# ou6_cs-ctrl_V1_1.net
KiCad netlist of a schematic drawn in EAGLE
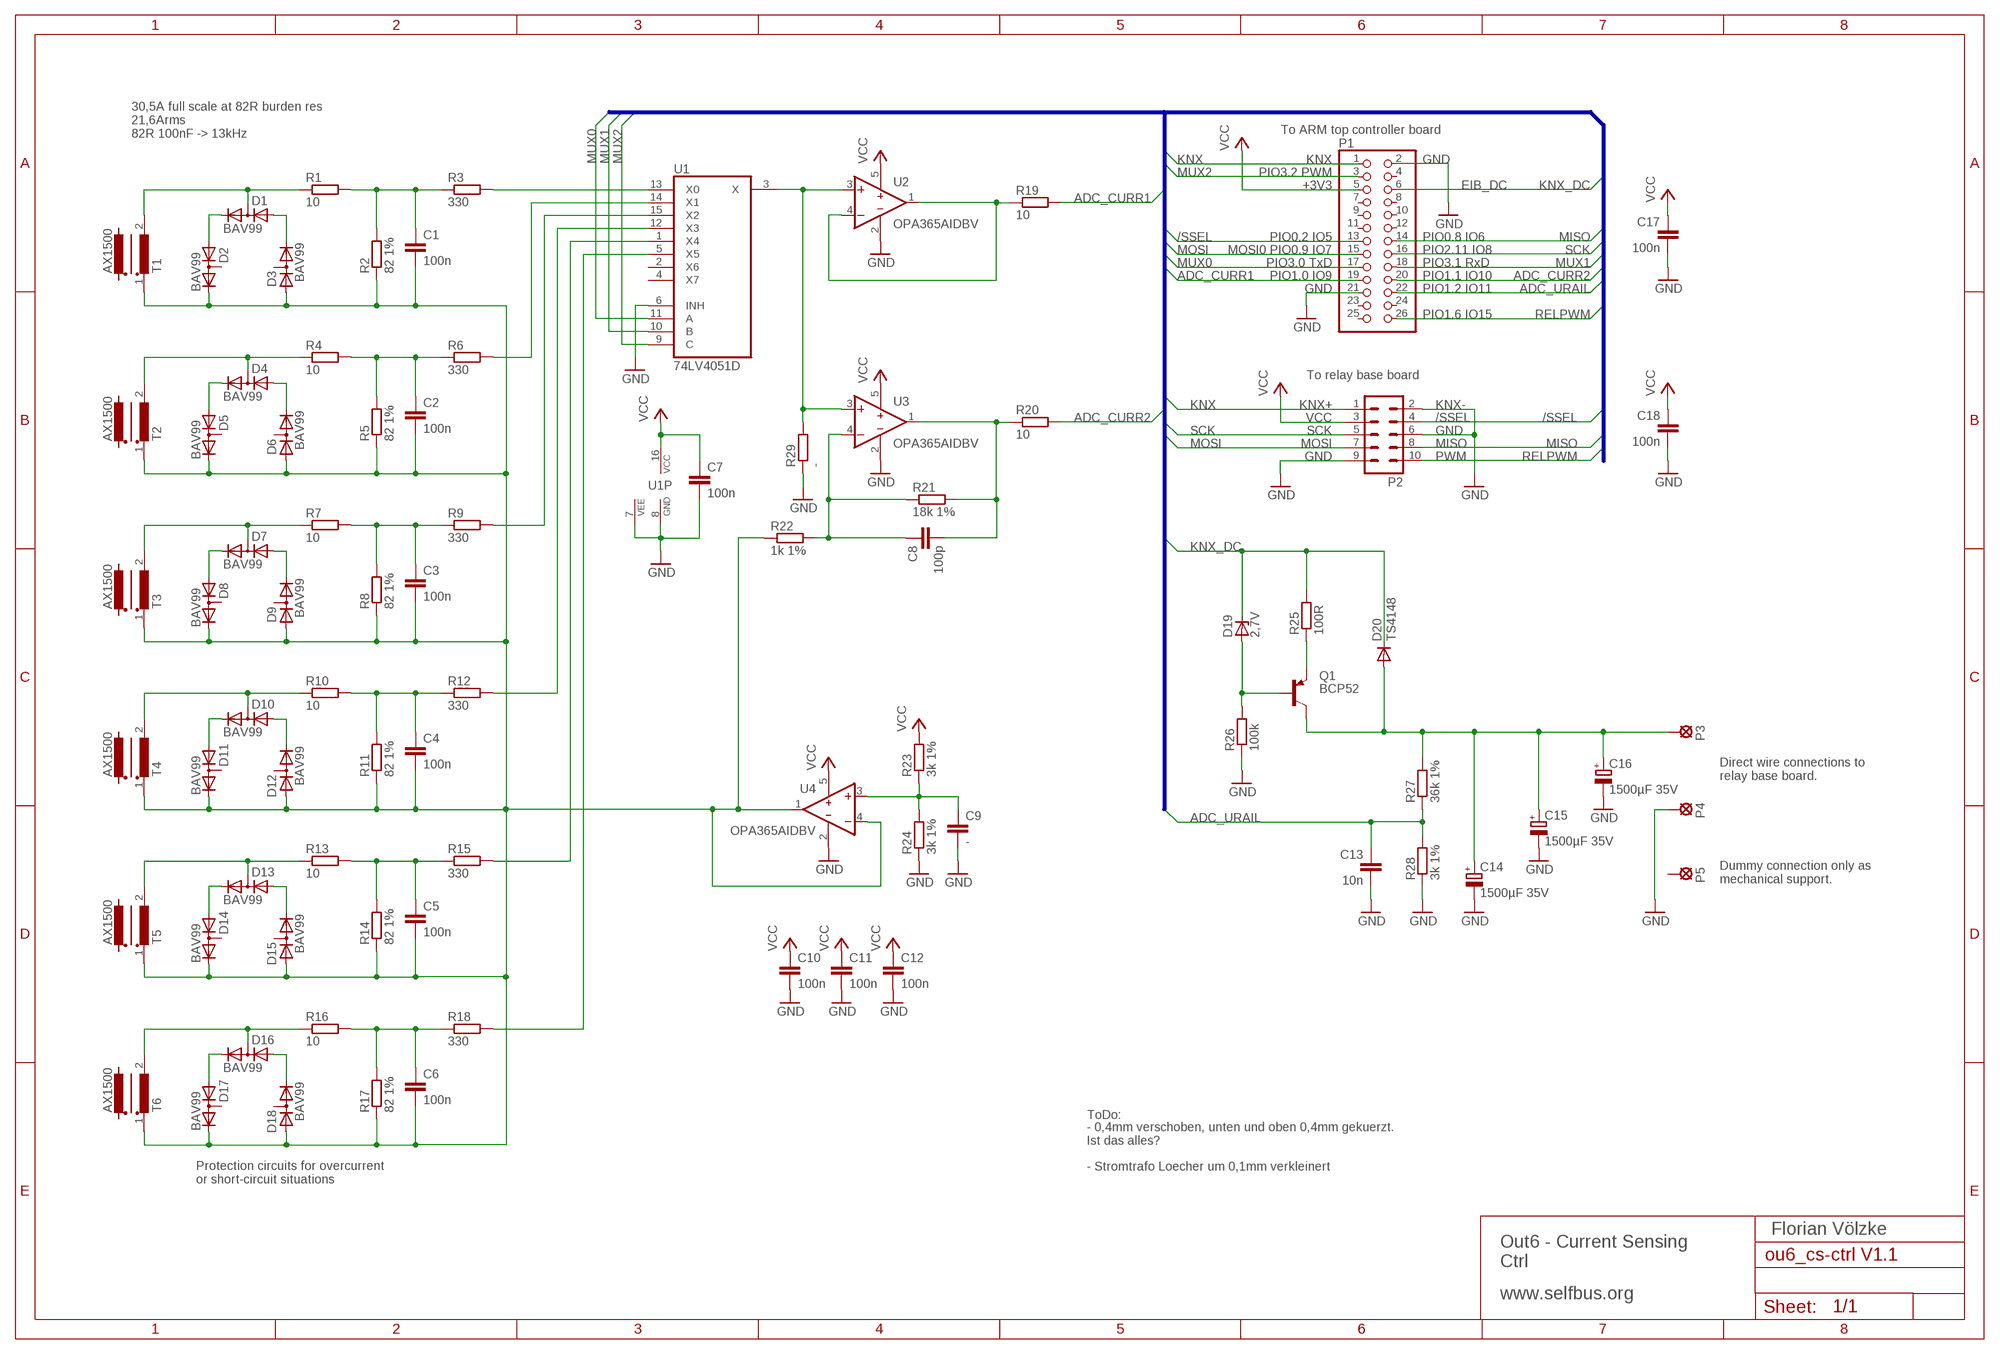
[diagram p0: schematic, sheet 1]

(export (version "E")
  (design (tool "Eeschema 10.0.6"))
  (components
    (comp (ref "C1")
      (value "100n")
      (footprint "eagle-import:R0805M")
      (libsource (lib "eagle-import") (part "C-EUC0805M"))
    )
    (comp (ref "C2")
      (value "100n")
      (footprint "eagle-import:R0805M")
      (libsource (lib "eagle-import") (part "C-EUC0805M"))
    )
    (comp (ref "C3")
      (value "100n")
      (footprint "eagle-import:R0805M")
      (libsource (lib "eagle-import") (part "C-EUC0805M"))
    )
    (comp (ref "C4")
      (value "100n")
      (footprint "eagle-import:R0805M")
      (libsource (lib "eagle-import") (part "C-EUC0805M"))
    )
    (comp (ref "C5")
      (value "100n")
      (footprint "eagle-import:R0805M")
      (libsource (lib "eagle-import") (part "C-EUC0805M"))
    )
    (comp (ref "C6")
      (value "100n")
      (footprint "eagle-import:R0805M")
      (libsource (lib "eagle-import") (part "C-EUC0805M"))
    )
    (comp (ref "C7")
      (value "100n")
      (footprint "eagle-import:R0805M")
      (libsource (lib "eagle-import") (part "C-EUC0805M"))
    )
    (comp (ref "C8")
      (value "100p")
      (footprint "eagle-import:R0805M")
      (libsource (lib "eagle-import") (part "C-EUC0805M"))
    )
    (comp (ref "C9")
      (value "-")
      (footprint "eagle-import:R0805M")
      (libsource (lib "eagle-import") (part "C-EUC0805M"))
    )
    (comp (ref "C10")
      (value "100n")
      (footprint "eagle-import:R0805M")
      (libsource (lib "eagle-import") (part "C-EUC0805M"))
    )
    (comp (ref "C11")
      (value "100n")
      (footprint "eagle-import:R0805M")
      (libsource (lib "eagle-import") (part "C-EUC0805M"))
    )
    (comp (ref "C12")
      (value "100n")
      (footprint "eagle-import:R0805M")
      (libsource (lib "eagle-import") (part "C-EUC0805M"))
    )
    (comp (ref "C13")
      (value "10n")
      (footprint "eagle-import:R0805M")
      (libsource (lib "eagle-import") (part "C-EUC0805M"))
    )
    (comp (ref "C14")
      (value "1500µF 35V")
      (footprint "eagle-import:E5-13-30")
      (libsource (lib "eagle-import") (part "CPOL-EUE5-13-30"))
    )
    (comp (ref "C15")
      (value "1500µF 35V")
      (footprint "eagle-import:E5-13-30")
      (libsource (lib "eagle-import") (part "CPOL-EUE5-13-30"))
    )
    (comp (ref "C16")
      (value "1500µF 35V")
      (footprint "eagle-import:E5-13-30")
      (libsource (lib "eagle-import") (part "CPOL-EUE5-13-30"))
    )
    (comp (ref "C17")
      (value "100n")
      (footprint "eagle-import:R0805M")
      (libsource (lib "eagle-import") (part "C-EUC0805M"))
    )
    (comp (ref "C18")
      (value "100n")
      (footprint "eagle-import:R0805M")
      (libsource (lib "eagle-import") (part "C-EUC0805M"))
    )
    (comp (ref "D1")
      (value "BAV99")
      (footprint "eagle-import:SOT23")
      (libsource (lib "eagle-import") (part "DIODE_2CACA-SOT23"))
    )
    (comp (ref "D2")
      (value "BAV99")
      (footprint "eagle-import:SOT23")
      (libsource (lib "eagle-import") (part "DIODE_2CACA-SOT23"))
    )
    (comp (ref "D3")
      (value "BAV99")
      (footprint "eagle-import:SOT23")
      (libsource (lib "eagle-import") (part "DIODE_2CACA-SOT23"))
    )
    (comp (ref "D4")
      (value "BAV99")
      (footprint "eagle-import:SOT23")
      (libsource (lib "eagle-import") (part "DIODE_2CACA-SOT23"))
    )
    (comp (ref "D5")
      (value "BAV99")
      (footprint "eagle-import:SOT23")
      (libsource (lib "eagle-import") (part "DIODE_2CACA-SOT23"))
    )
    (comp (ref "D6")
      (value "BAV99")
      (footprint "eagle-import:SOT23")
      (libsource (lib "eagle-import") (part "DIODE_2CACA-SOT23"))
    )
    (comp (ref "D7")
      (value "BAV99")
      (footprint "eagle-import:SOT23")
      (libsource (lib "eagle-import") (part "DIODE_2CACA-SOT23"))
    )
    (comp (ref "D8")
      (value "BAV99")
      (footprint "eagle-import:SOT23")
      (libsource (lib "eagle-import") (part "DIODE_2CACA-SOT23"))
    )
    (comp (ref "D9")
      (value "BAV99")
      (footprint "eagle-import:SOT23")
      (libsource (lib "eagle-import") (part "DIODE_2CACA-SOT23"))
    )
    (comp (ref "D10")
      (value "BAV99")
      (footprint "eagle-import:SOT23")
      (libsource (lib "eagle-import") (part "DIODE_2CACA-SOT23"))
    )
    (comp (ref "D11")
      (value "BAV99")
      (footprint "eagle-import:SOT23")
      (libsource (lib "eagle-import") (part "DIODE_2CACA-SOT23"))
    )
    (comp (ref "D12")
      (value "BAV99")
      (footprint "eagle-import:SOT23")
      (libsource (lib "eagle-import") (part "DIODE_2CACA-SOT23"))
    )
    (comp (ref "D13")
      (value "BAV99")
      (footprint "eagle-import:SOT23")
      (libsource (lib "eagle-import") (part "DIODE_2CACA-SOT23"))
    )
    (comp (ref "D14")
      (value "BAV99")
      (footprint "eagle-import:SOT23")
      (libsource (lib "eagle-import") (part "DIODE_2CACA-SOT23"))
    )
    (comp (ref "D15")
      (value "BAV99")
      (footprint "eagle-import:SOT23")
      (libsource (lib "eagle-import") (part "DIODE_2CACA-SOT23"))
    )
    (comp (ref "D16")
      (value "BAV99")
      (footprint "eagle-import:SOT23")
      (libsource (lib "eagle-import") (part "DIODE_2CACA-SOT23"))
    )
    (comp (ref "D17")
      (value "BAV99")
      (footprint "eagle-import:SOT23")
      (libsource (lib "eagle-import") (part "DIODE_2CACA-SOT23"))
    )
    (comp (ref "D18")
      (value "BAV99")
      (footprint "eagle-import:SOT23")
      (libsource (lib "eagle-import") (part "DIODE_2CACA-SOT23"))
    )
    (comp (ref "D19")
      (value "2,7V")
      (footprint "eagle-import:SOT23")
      (libsource (lib "eagle-import") (part "ZENER-DIODESOT23"))
    )
    (comp (ref "D20")
      (value "TS4148")
      (footprint "eagle-import:D0805")
      (libsource (lib "eagle-import") (part "DIODE-D0805"))
    )
    (comp (ref "P1")
      (value "PINHD-2X13SMD")
      (footprint "eagle-import:2X13SMD")
      (libsource (lib "eagle-import") (part "PINHD-2X13SMD"))
    )
    (comp (ref "P2")
      (value "ML10")
      (footprint "eagle-import:ML10")
      (libsource (lib "eagle-import") (part "ML10"))
    )
    (comp (ref "P3")
      (value "SE1.5")
      (footprint "eagle-import:SE15")
      (libsource (lib "eagle-import") (part "SE1.5"))
    )
    (comp (ref "P4")
      (value "SE1.5")
      (footprint "eagle-import:SE15")
      (libsource (lib "eagle-import") (part "SE1.5"))
    )
    (comp (ref "P5")
      (value "SE1.5")
      (footprint "eagle-import:SE15")
      (libsource (lib "eagle-import") (part "SE1.5"))
    )
    (comp (ref "Q1")
      (value "BCP52")
      (footprint "eagle-import:SOT223")
      (libsource (lib "eagle-import") (part "FZT753SMD"))
    )
    (comp (ref "R1")
      (value "10")
      (footprint "eagle-import:R0805M")
      (libsource (lib "eagle-import") (part "R-EU_R0805M"))
    )
    (comp (ref "R2")
      (value "82 1%")
      (footprint "eagle-import:R0805M")
      (libsource (lib "eagle-import") (part "R-EU_R0805M"))
    )
    (comp (ref "R3")
      (value "330")
      (footprint "eagle-import:R0805M")
      (libsource (lib "eagle-import") (part "R-EU_R0805M"))
    )
    (comp (ref "R4")
      (value "10")
      (footprint "eagle-import:R0805M")
      (libsource (lib "eagle-import") (part "R-EU_R0805M"))
    )
    (comp (ref "R5")
      (value "82 1%")
      (footprint "eagle-import:R0805M")
      (libsource (lib "eagle-import") (part "R-EU_R0805M"))
    )
    (comp (ref "R6")
      (value "330")
      (footprint "eagle-import:R0805M")
      (libsource (lib "eagle-import") (part "R-EU_R0805M"))
    )
    (comp (ref "R7")
      (value "10")
      (footprint "eagle-import:R0805M")
      (libsource (lib "eagle-import") (part "R-EU_R0805M"))
    )
    (comp (ref "R8")
      (value "82 1%")
      (footprint "eagle-import:R0805M")
      (libsource (lib "eagle-import") (part "R-EU_R0805M"))
    )
    (comp (ref "R9")
      (value "330")
      (footprint "eagle-import:R0805M")
      (libsource (lib "eagle-import") (part "R-EU_R0805M"))
    )
    (comp (ref "R10")
      (value "10")
      (footprint "eagle-import:R0805M")
      (libsource (lib "eagle-import") (part "R-EU_R0805M"))
    )
    (comp (ref "R11")
      (value "82 1%")
      (footprint "eagle-import:R0805M")
      (libsource (lib "eagle-import") (part "R-EU_R0805M"))
    )
    (comp (ref "R12")
      (value "330")
      (footprint "eagle-import:R0805M")
      (libsource (lib "eagle-import") (part "R-EU_R0805M"))
    )
    (comp (ref "R13")
      (value "10")
      (footprint "eagle-import:R0805M")
      (libsource (lib "eagle-import") (part "R-EU_R0805M"))
    )
    (comp (ref "R14")
      (value "82 1%")
      (footprint "eagle-import:R0805M")
      (libsource (lib "eagle-import") (part "R-EU_R0805M"))
    )
    (comp (ref "R15")
      (value "330")
      (footprint "eagle-import:R0805M")
      (libsource (lib "eagle-import") (part "R-EU_R0805M"))
    )
    (comp (ref "R16")
      (value "10")
      (footprint "eagle-import:R0805M")
      (libsource (lib "eagle-import") (part "R-EU_R0805M"))
    )
    (comp (ref "R17")
      (value "82 1%")
      (footprint "eagle-import:R0805M")
      (libsource (lib "eagle-import") (part "R-EU_R0805M"))
    )
    (comp (ref "R18")
      (value "330")
      (footprint "eagle-import:R0805M")
      (libsource (lib "eagle-import") (part "R-EU_R0805M"))
    )
    (comp (ref "R19")
      (value "10")
      (footprint "eagle-import:R0805M")
      (libsource (lib "eagle-import") (part "R-EU_R0805M"))
    )
    (comp (ref "R20")
      (value "10")
      (footprint "eagle-import:R0805M")
      (libsource (lib "eagle-import") (part "R-EU_R0805M"))
    )
    (comp (ref "R21")
      (value "18k 1%")
      (footprint "eagle-import:R0805M")
      (libsource (lib "eagle-import") (part "R-EU_R0805M"))
    )
    (comp (ref "R22")
      (value "1k 1%")
      (footprint "eagle-import:R0805M")
      (libsource (lib "eagle-import") (part "R-EU_R0805M"))
    )
    (comp (ref "R23")
      (value "3k 1%")
      (footprint "eagle-import:R0805M")
      (libsource (lib "eagle-import") (part "R-EU_R0805M"))
    )
    (comp (ref "R24")
      (value "3k 1%")
      (footprint "eagle-import:R0805M")
      (libsource (lib "eagle-import") (part "R-EU_R0805M"))
    )
    (comp (ref "R25")
      (value "100R")
      (footprint "eagle-import:R0805M")
      (libsource (lib "eagle-import") (part "R-EU_R0805M"))
    )
    (comp (ref "R26")
      (value "100k")
      (footprint "eagle-import:R0805M")
      (libsource (lib "eagle-import") (part "R-EU_R0805M"))
    )
    (comp (ref "R27")
      (value "36k 1%")
      (footprint "eagle-import:R0805M")
      (libsource (lib "eagle-import") (part "R-EU_R0805M"))
    )
    (comp (ref "R28")
      (value "3k 1%")
      (footprint "eagle-import:R0805M")
      (libsource (lib "eagle-import") (part "R-EU_R0805M"))
    )
    (comp (ref "R29")
      (value "-")
      (footprint "eagle-import:R0805M")
      (libsource (lib "eagle-import") (part "R-EU_R0805M"))
    )
    (comp (ref "T1")
      (value "AX1500")
      (footprint "eagle-import:SMALLXFORMER")
      (libsource (lib "eagle-import") (part "STROMWANDLERTALEMA_AX1500"))
    )
    (comp (ref "T2")
      (value "AX1500")
      (footprint "eagle-import:SMALLXFORMER")
      (libsource (lib "eagle-import") (part "STROMWANDLERTALEMA_AX1500"))
    )
    (comp (ref "T3")
      (value "AX1500")
      (footprint "eagle-import:SMALLXFORMER")
      (libsource (lib "eagle-import") (part "STROMWANDLERTALEMA_AX1500"))
    )
    (comp (ref "T4")
      (value "AX1500")
      (footprint "eagle-import:SMALLXFORMER")
      (libsource (lib "eagle-import") (part "STROMWANDLERTALEMA_AX1500"))
    )
    (comp (ref "T5")
      (value "AX1500")
      (footprint "eagle-import:SMALLXFORMER")
      (libsource (lib "eagle-import") (part "STROMWANDLERTALEMA_AX1500"))
    )
    (comp (ref "T6")
      (value "AX1500")
      (footprint "eagle-import:SMALLXFORMER")
      (libsource (lib "eagle-import") (part "STROMWANDLERTALEMA_AX1500"))
    )
    (comp (ref "U1")
      (value "74LV4051D")
      (footprint "eagle-import:SO16")
      (libsource (lib "eagle-import") (part "4051D"))
    )
    (comp (ref "U2")
      (value "OPA365AIDBV")
      (footprint "eagle-import:SOT23-5")
      (libsource (lib "eagle-import") (part "LTC2050CS5"))
    )
    (comp (ref "U3")
      (value "OPA365AIDBV")
      (footprint "eagle-import:SOT23-5")
      (libsource (lib "eagle-import") (part "LTC2050CS5"))
    )
    (comp (ref "U4")
      (value "OPA365AIDBV")
      (footprint "eagle-import:SOT23-5")
      (libsource (lib "eagle-import") (part "LTC2050CS5"))
    )
  )
  (nets
    (net (code "1") (name "/ADC_CURR1") (class "Default")
      (node (ref "P1") (pin "19") (pinfunction "19_19") (pintype "passive"))
      (node (ref "R19") (pin "2") (pinfunction "2_2") (pintype "passive"))
    )
    (net (code "2") (name "/ADC_CURR2") (class "Default")
      (node (ref "P1") (pin "20") (pinfunction "20_20") (pintype "passive"))
      (node (ref "R20") (pin "2") (pinfunction "2_2") (pintype "passive"))
    )
    (net (code "3") (name "/ADC_URAIL") (class "Default")
      (node (ref "C13") (pin "1") (pinfunction "1_1") (pintype "passive"))
      (node (ref "P1") (pin "22") (pinfunction "22_22") (pintype "passive"))
      (node (ref "R27") (pin "1") (pinfunction "1_1") (pintype "passive"))
      (node (ref "R28") (pin "2") (pinfunction "2_2") (pintype "passive"))
    )
    (net (code "4") (name "/KNX") (class "Default")
      (node (ref "P1") (pin "1") (pinfunction "1_1") (pintype "passive"))
      (node (ref "P2") (pin "1") (pinfunction "1_1") (pintype "passive"))
    )
    (net (code "5") (name "/KNX_DC") (class "Default")
      (node (ref "D19") (pin "3") (pinfunction "C_3") (pintype "passive"))
      (node (ref "D20") (pin "C") (pinfunction "C_C") (pintype "passive"))
      (node (ref "P1") (pin "6") (pinfunction "6_6") (pintype "passive"))
      (node (ref "R25") (pin "2") (pinfunction "2_2") (pintype "passive"))
    )
    (net (code "6") (name "/MISO") (class "Default")
      (node (ref "P1") (pin "14") (pinfunction "14_14") (pintype "passive"))
      (node (ref "P2") (pin "8") (pinfunction "8_8") (pintype "passive"))
    )
    (net (code "7") (name "/MOSI") (class "Default")
      (node (ref "P1") (pin "15") (pinfunction "15_15") (pintype "passive"))
      (node (ref "P2") (pin "7") (pinfunction "7_7") (pintype "passive"))
    )
    (net (code "8") (name "/MUX0") (class "Default")
      (node (ref "P1") (pin "17") (pinfunction "17_17") (pintype "passive"))
      (node (ref "U1") (pin "11") (pinfunction "A_11") (pintype "input"))
    )
    (net (code "9") (name "/MUX1") (class "Default")
      (node (ref "P1") (pin "18") (pinfunction "18_18") (pintype "passive"))
      (node (ref "U1") (pin "10") (pinfunction "B_10") (pintype "input"))
    )
    (net (code "10") (name "/MUX2") (class "Default")
      (node (ref "P1") (pin "3") (pinfunction "3_3") (pintype "passive"))
      (node (ref "U1") (pin "9") (pinfunction "C_9") (pintype "input"))
    )
    (net (code "11") (name "/RELPWM") (class "Default")
      (node (ref "P1") (pin "26") (pinfunction "26_26") (pintype "passive"))
      (node (ref "P2") (pin "10") (pinfunction "10_10") (pintype "passive"))
    )
    (net (code "12") (name "/SCK") (class "Default")
      (node (ref "P1") (pin "16") (pinfunction "16_16") (pintype "passive"))
      (node (ref "P2") (pin "5") (pinfunction "5_5") (pintype "passive"))
    )
    (net (code "13") (name "/{slash}SSEL") (class "Default")
      (node (ref "P1") (pin "13") (pinfunction "13_13") (pintype "passive"))
      (node (ref "P2") (pin "4") (pinfunction "4_4") (pintype "passive"))
    )
    (net (code "14") (name "GND") (class "Default")
      (node (ref "C10") (pin "2") (pinfunction "2_2") (pintype "passive"))
      (node (ref "C11") (pin "2") (pinfunction "2_2") (pintype "passive"))
      (node (ref "C12") (pin "2") (pinfunction "2_2") (pintype "passive"))
      (node (ref "C13") (pin "2") (pinfunction "2_2") (pintype "passive"))
      (node (ref "C14") (pin "-") (pinfunction "-_-") (pintype "passive"))
      (node (ref "C15") (pin "-") (pinfunction "-_-") (pintype "passive"))
      (node (ref "C16") (pin "-") (pinfunction "-_-") (pintype "passive"))
      (node (ref "C17") (pin "2") (pinfunction "2_2") (pintype "passive"))
      (node (ref "C18") (pin "2") (pinfunction "2_2") (pintype "passive"))
      (node (ref "C7") (pin "2") (pinfunction "2_2") (pintype "passive"))
      (node (ref "C9") (pin "2") (pinfunction "2_2") (pintype "passive"))
      (node (ref "P1") (pin "2") (pinfunction "2_2") (pintype "passive"))
      (node (ref "P1") (pin "21") (pinfunction "21_21") (pintype "passive"))
      (node (ref "P2") (pin "2") (pinfunction "2_2") (pintype "passive"))
      (node (ref "P2") (pin "6") (pinfunction "6_6") (pintype "passive"))
      (node (ref "P2") (pin "9") (pinfunction "9_9") (pintype "passive"))
      (node (ref "P4") (pin "MP") (pinfunction "MP_MP") (pintype "passive"))
      (node (ref "R24") (pin "1") (pinfunction "1_1") (pintype "passive"))
      (node (ref "R26") (pin "1") (pinfunction "1_1") (pintype "passive"))
      (node (ref "R28") (pin "1") (pinfunction "1_1") (pintype "passive"))
      (node (ref "R29") (pin "1") (pinfunction "1_1") (pintype "passive"))
      (node (ref "U1") (pin "6") (pinfunction "INH_6") (pintype "input"))
      (node (ref "U1") (pin "7") (pinfunction "VEE_7") (pintype "power_in"))
      (node (ref "U1") (pin "8") (pinfunction "GND_8") (pintype "power_in"))
      (node (ref "U2") (pin "2") (pinfunction "V-_2") (pintype "power_in"))
      (node (ref "U3") (pin "2") (pinfunction "V-_2") (pintype "power_in"))
      (node (ref "U4") (pin "2") (pinfunction "V-_2") (pintype "power_in"))
    )
    (net (code "15") (name "Net-(C1-Pad1)") (class "Default")
      (node (ref "C1") (pin "1") (pinfunction "1_1") (pintype "passive"))
      (node (ref "R1") (pin "2") (pinfunction "2_2") (pintype "passive"))
      (node (ref "R2") (pin "2") (pinfunction "2_2") (pintype "passive"))
      (node (ref "R3") (pin "1") (pinfunction "1_1") (pintype "passive"))
    )
    (net (code "16") (name "Net-(C2-Pad1)") (class "Default")
      (node (ref "C2") (pin "1") (pinfunction "1_1") (pintype "passive"))
      (node (ref "R4") (pin "2") (pinfunction "2_2") (pintype "passive"))
      (node (ref "R5") (pin "2") (pinfunction "2_2") (pintype "passive"))
      (node (ref "R6") (pin "1") (pinfunction "1_1") (pintype "passive"))
    )
    (net (code "17") (name "Net-(C3-Pad1)") (class "Default")
      (node (ref "C3") (pin "1") (pinfunction "1_1") (pintype "passive"))
      (node (ref "R7") (pin "2") (pinfunction "2_2") (pintype "passive"))
      (node (ref "R8") (pin "2") (pinfunction "2_2") (pintype "passive"))
      (node (ref "R9") (pin "1") (pinfunction "1_1") (pintype "passive"))
    )
    (net (code "18") (name "Net-(C4-Pad1)") (class "Default")
      (node (ref "C4") (pin "1") (pinfunction "1_1") (pintype "passive"))
      (node (ref "R10") (pin "2") (pinfunction "2_2") (pintype "passive"))
      (node (ref "R11") (pin "2") (pinfunction "2_2") (pintype "passive"))
      (node (ref "R12") (pin "1") (pinfunction "1_1") (pintype "passive"))
    )
    (net (code "19") (name "Net-(C5-Pad1)") (class "Default")
      (node (ref "C5") (pin "1") (pinfunction "1_1") (pintype "passive"))
      (node (ref "R13") (pin "2") (pinfunction "2_2") (pintype "passive"))
      (node (ref "R14") (pin "2") (pinfunction "2_2") (pintype "passive"))
      (node (ref "R15") (pin "1") (pinfunction "1_1") (pintype "passive"))
    )
    (net (code "20") (name "Net-(C6-Pad1)") (class "Default")
      (node (ref "C6") (pin "1") (pinfunction "1_1") (pintype "passive"))
      (node (ref "R16") (pin "2") (pinfunction "2_2") (pintype "passive"))
      (node (ref "R17") (pin "2") (pinfunction "2_2") (pintype "passive"))
      (node (ref "R18") (pin "1") (pinfunction "1_1") (pintype "passive"))
    )
    (net (code "21") (name "Net-(C14-Pad+)") (class "Default")
      (node (ref "C14") (pin "+") (pinfunction "+_+") (pintype "passive"))
      (node (ref "C15") (pin "+") (pinfunction "+_+") (pintype "passive"))
      (node (ref "C16") (pin "+") (pinfunction "+_+") (pintype "passive"))
      (node (ref "D20") (pin "A") (pinfunction "A_A") (pintype "passive"))
      (node (ref "P3") (pin "MP") (pinfunction "MP_MP") (pintype "passive"))
      (node (ref "Q1") (pin "2") (pinfunction "C_2") (pintype "passive"))
      (node (ref "Q1") (pin "4") (pinfunction "C_4") (pintype "passive"))
      (node (ref "R27") (pin "2") (pinfunction "2_2") (pintype "passive"))
    )
    (net (code "22") (name "Net-(D1-A)") (class "Default")
      (node (ref "D1") (pin "1") (pinfunction "A_1") (pintype "passive"))
      (node (ref "D3") (pin "2") (pinfunction "C_2") (pintype "passive"))
    )
    (net (code "23") (name "Net-(D1-AC)") (class "Default")
      (node (ref "D1") (pin "3") (pinfunction "AC_3") (pintype "passive"))
      (node (ref "R1") (pin "1") (pinfunction "1_1") (pintype "passive"))
      (node (ref "T1") (pin "2") (pinfunction "W1E_2") (pintype "passive"))
    )
    (net (code "24") (name "Net-(D1-C)") (class "Default")
      (node (ref "D1") (pin "2") (pinfunction "C_2") (pintype "passive"))
      (node (ref "D2") (pin "1") (pinfunction "A_1") (pintype "passive"))
    )
    (net (code "25") (name "Net-(D4-A)") (class "Default")
      (node (ref "D4") (pin "1") (pinfunction "A_1") (pintype "passive"))
      (node (ref "D6") (pin "2") (pinfunction "C_2") (pintype "passive"))
    )
    (net (code "26") (name "Net-(D4-AC)") (class "Default")
      (node (ref "D4") (pin "3") (pinfunction "AC_3") (pintype "passive"))
      (node (ref "R4") (pin "1") (pinfunction "1_1") (pintype "passive"))
      (node (ref "T2") (pin "2") (pinfunction "W1E_2") (pintype "passive"))
    )
    (net (code "27") (name "Net-(D4-C)") (class "Default")
      (node (ref "D4") (pin "2") (pinfunction "C_2") (pintype "passive"))
      (node (ref "D5") (pin "1") (pinfunction "A_1") (pintype "passive"))
    )
    (net (code "28") (name "Net-(D7-A)") (class "Default")
      (node (ref "D7") (pin "1") (pinfunction "A_1") (pintype "passive"))
      (node (ref "D9") (pin "2") (pinfunction "C_2") (pintype "passive"))
    )
    (net (code "29") (name "Net-(D7-AC)") (class "Default")
      (node (ref "D7") (pin "3") (pinfunction "AC_3") (pintype "passive"))
      (node (ref "R7") (pin "1") (pinfunction "1_1") (pintype "passive"))
      (node (ref "T3") (pin "2") (pinfunction "W1E_2") (pintype "passive"))
    )
    (net (code "30") (name "Net-(D7-C)") (class "Default")
      (node (ref "D7") (pin "2") (pinfunction "C_2") (pintype "passive"))
      (node (ref "D8") (pin "1") (pinfunction "A_1") (pintype "passive"))
    )
    (net (code "31") (name "Net-(D10-A)") (class "Default")
      (node (ref "D10") (pin "1") (pinfunction "A_1") (pintype "passive"))
      (node (ref "D12") (pin "2") (pinfunction "C_2") (pintype "passive"))
    )
    (net (code "32") (name "Net-(D10-AC)") (class "Default")
      (node (ref "D10") (pin "3") (pinfunction "AC_3") (pintype "passive"))
      (node (ref "R10") (pin "1") (pinfunction "1_1") (pintype "passive"))
      (node (ref "T4") (pin "2") (pinfunction "W1E_2") (pintype "passive"))
    )
    (net (code "33") (name "Net-(D10-C)") (class "Default")
      (node (ref "D10") (pin "2") (pinfunction "C_2") (pintype "passive"))
      (node (ref "D11") (pin "1") (pinfunction "A_1") (pintype "passive"))
    )
    (net (code "34") (name "Net-(D11-C)") (class "Default")
      (node (ref "C1") (pin "2") (pinfunction "2_2") (pintype "passive"))
      (node (ref "C2") (pin "2") (pinfunction "2_2") (pintype "passive"))
      (node (ref "C3") (pin "2") (pinfunction "2_2") (pintype "passive"))
      (node (ref "C4") (pin "2") (pinfunction "2_2") (pintype "passive"))
      (node (ref "C5") (pin "2") (pinfunction "2_2") (pintype "passive"))
      (node (ref "C6") (pin "2") (pinfunction "2_2") (pintype "passive"))
      (node (ref "D11") (pin "2") (pinfunction "C_2") (pintype "passive"))
      (node (ref "D12") (pin "1") (pinfunction "A_1") (pintype "passive"))
      (node (ref "D14") (pin "2") (pinfunction "C_2") (pintype "passive"))
      (node (ref "D15") (pin "1") (pinfunction "A_1") (pintype "passive"))
      (node (ref "D17") (pin "2") (pinfunction "C_2") (pintype "passive"))
      (node (ref "D18") (pin "1") (pinfunction "A_1") (pintype "passive"))
      (node (ref "D2") (pin "2") (pinfunction "C_2") (pintype "passive"))
      (node (ref "D3") (pin "1") (pinfunction "A_1") (pintype "passive"))
      (node (ref "D5") (pin "2") (pinfunction "C_2") (pintype "passive"))
      (node (ref "D6") (pin "1") (pinfunction "A_1") (pintype "passive"))
      (node (ref "D8") (pin "2") (pinfunction "C_2") (pintype "passive"))
      (node (ref "D9") (pin "1") (pinfunction "A_1") (pintype "passive"))
      (node (ref "R11") (pin "1") (pinfunction "1_1") (pintype "passive"))
      (node (ref "R14") (pin "1") (pinfunction "1_1") (pintype "passive"))
      (node (ref "R17") (pin "1") (pinfunction "1_1") (pintype "passive"))
      (node (ref "R2") (pin "1") (pinfunction "1_1") (pintype "passive"))
      (node (ref "R22") (pin "1") (pinfunction "1_1") (pintype "passive"))
      (node (ref "R5") (pin "1") (pinfunction "1_1") (pintype "passive"))
      (node (ref "R8") (pin "1") (pinfunction "1_1") (pintype "passive"))
      (node (ref "T1") (pin "1") (pinfunction "W1A_1") (pintype "passive"))
      (node (ref "T2") (pin "1") (pinfunction "W1A_1") (pintype "passive"))
      (node (ref "T3") (pin "1") (pinfunction "W1A_1") (pintype "passive"))
      (node (ref "T4") (pin "1") (pinfunction "W1A_1") (pintype "passive"))
      (node (ref "T5") (pin "1") (pinfunction "W1A_1") (pintype "passive"))
      (node (ref "T6") (pin "1") (pinfunction "W1A_1") (pintype "passive"))
      (node (ref "U4") (pin "1") (pinfunction "OUT_1") (pintype "output"))
      (node (ref "U4") (pin "4") (pinfunction "-IN_4") (pintype "input"))
    )
    (net (code "35") (name "Net-(D13-A)") (class "Default")
      (node (ref "D13") (pin "1") (pinfunction "A_1") (pintype "passive"))
      (node (ref "D15") (pin "2") (pinfunction "C_2") (pintype "passive"))
    )
    (net (code "36") (name "Net-(D13-AC)") (class "Default")
      (node (ref "D13") (pin "3") (pinfunction "AC_3") (pintype "passive"))
      (node (ref "R13") (pin "1") (pinfunction "1_1") (pintype "passive"))
      (node (ref "T5") (pin "2") (pinfunction "W1E_2") (pintype "passive"))
    )
    (net (code "37") (name "Net-(D13-C)") (class "Default")
      (node (ref "D13") (pin "2") (pinfunction "C_2") (pintype "passive"))
      (node (ref "D14") (pin "1") (pinfunction "A_1") (pintype "passive"))
    )
    (net (code "38") (name "Net-(D16-A)") (class "Default")
      (node (ref "D16") (pin "1") (pinfunction "A_1") (pintype "passive"))
      (node (ref "D18") (pin "2") (pinfunction "C_2") (pintype "passive"))
    )
    (net (code "39") (name "Net-(D16-AC)") (class "Default")
      (node (ref "D16") (pin "3") (pinfunction "AC_3") (pintype "passive"))
      (node (ref "R16") (pin "1") (pinfunction "1_1") (pintype "passive"))
      (node (ref "T6") (pin "2") (pinfunction "W1E_2") (pintype "passive"))
    )
    (net (code "40") (name "Net-(D16-C)") (class "Default")
      (node (ref "D16") (pin "2") (pinfunction "C_2") (pintype "passive"))
      (node (ref "D17") (pin "1") (pinfunction "A_1") (pintype "passive"))
    )
    (net (code "41") (name "Net-(D19-A)") (class "Default")
      (node (ref "D19") (pin "1") (pinfunction "A_1") (pintype "passive"))
      (node (ref "Q1") (pin "1") (pinfunction "B_1") (pintype "passive"))
      (node (ref "R26") (pin "2") (pinfunction "2_2") (pintype "passive"))
    )
    (net (code "42") (name "Net-(Q1-E)") (class "Default")
      (node (ref "Q1") (pin "3") (pinfunction "E_3") (pintype "passive"))
      (node (ref "R25") (pin "1") (pinfunction "1_1") (pintype "passive"))
    )
    (net (code "43") (name "Net-(U1A-X)") (class "Default")
      (node (ref "R29") (pin "2") (pinfunction "2_2") (pintype "passive"))
      (node (ref "U1") (pin "3") (pinfunction "X_3") (pintype "bidirectional"))
      (node (ref "U2") (pin "3") (pinfunction "+IN_3") (pintype "input"))
      (node (ref "U3") (pin "3") (pinfunction "+IN_3") (pintype "input"))
    )
    (net (code "44") (name "Net-(U1A-X0)") (class "Default")
      (node (ref "R3") (pin "2") (pinfunction "2_2") (pintype "passive"))
      (node (ref "U1") (pin "13") (pinfunction "X0_13") (pintype "bidirectional"))
    )
    (net (code "45") (name "Net-(U1A-X1)") (class "Default")
      (node (ref "R6") (pin "2") (pinfunction "2_2") (pintype "passive"))
      (node (ref "U1") (pin "14") (pinfunction "X1_14") (pintype "bidirectional"))
    )
    (net (code "46") (name "Net-(U1A-X2)") (class "Default")
      (node (ref "R9") (pin "2") (pinfunction "2_2") (pintype "passive"))
      (node (ref "U1") (pin "15") (pinfunction "X2_15") (pintype "bidirectional"))
    )
    (net (code "47") (name "Net-(U1A-X3)") (class "Default")
      (node (ref "R12") (pin "2") (pinfunction "2_2") (pintype "passive"))
      (node (ref "U1") (pin "12") (pinfunction "X3_12") (pintype "bidirectional"))
    )
    (net (code "48") (name "Net-(U1A-X4)") (class "Default")
      (node (ref "R15") (pin "2") (pinfunction "2_2") (pintype "passive"))
      (node (ref "U1") (pin "1") (pinfunction "X4_1") (pintype "bidirectional"))
    )
    (net (code "49") (name "Net-(U1A-X5)") (class "Default")
      (node (ref "R18") (pin "2") (pinfunction "2_2") (pintype "passive"))
      (node (ref "U1") (pin "5") (pinfunction "X5_5") (pintype "bidirectional"))
    )
    (net (code "50") (name "Net-(U2--IN)") (class "Default")
      (node (ref "R19") (pin "1") (pinfunction "1_1") (pintype "passive"))
      (node (ref "U2") (pin "1") (pinfunction "OUT_1") (pintype "output"))
      (node (ref "U2") (pin "4") (pinfunction "-IN_4") (pintype "input"))
    )
    (net (code "51") (name "Net-(U3--IN)") (class "Default")
      (node (ref "C8") (pin "1") (pinfunction "1_1") (pintype "passive"))
      (node (ref "R21") (pin "1") (pinfunction "1_1") (pintype "passive"))
      (node (ref "R22") (pin "2") (pinfunction "2_2") (pintype "passive"))
      (node (ref "U3") (pin "4") (pinfunction "-IN_4") (pintype "input"))
    )
    (net (code "52") (name "Net-(U3-OUT)") (class "Default")
      (node (ref "C8") (pin "2") (pinfunction "2_2") (pintype "passive"))
      (node (ref "R20") (pin "1") (pinfunction "1_1") (pintype "passive"))
      (node (ref "R21") (pin "2") (pinfunction "2_2") (pintype "passive"))
      (node (ref "U3") (pin "1") (pinfunction "OUT_1") (pintype "output"))
    )
    (net (code "53") (name "Net-(U4-+IN)") (class "Default")
      (node (ref "C9") (pin "1") (pinfunction "1_1") (pintype "passive"))
      (node (ref "R23") (pin "1") (pinfunction "1_1") (pintype "passive"))
      (node (ref "R24") (pin "2") (pinfunction "2_2") (pintype "passive"))
      (node (ref "U4") (pin "3") (pinfunction "+IN_3") (pintype "input"))
    )
    (net (code "54") (name "VCC") (class "Default")
      (node (ref "C10") (pin "1") (pinfunction "1_1") (pintype "passive"))
      (node (ref "C11") (pin "1") (pinfunction "1_1") (pintype "passive"))
      (node (ref "C12") (pin "1") (pinfunction "1_1") (pintype "passive"))
      (node (ref "C17") (pin "1") (pinfunction "1_1") (pintype "passive"))
      (node (ref "C18") (pin "1") (pinfunction "1_1") (pintype "passive"))
      (node (ref "C7") (pin "1") (pinfunction "1_1") (pintype "passive"))
      (node (ref "P1") (pin "5") (pinfunction "5_5") (pintype "passive"))
      (node (ref "P2") (pin "3") (pinfunction "3_3") (pintype "passive"))
      (node (ref "R23") (pin "2") (pinfunction "2_2") (pintype "passive"))
      (node (ref "U1") (pin "16") (pinfunction "VCC_16") (pintype "power_in"))
      (node (ref "U2") (pin "5") (pinfunction "V+_5") (pintype "power_in"))
      (node (ref "U3") (pin "5") (pinfunction "V+_5") (pintype "power_in"))
      (node (ref "U4") (pin "5") (pinfunction "V+_5") (pintype "power_in"))
    )
    (net (code "55") (name "unconnected-(D2-AC-Pad3)") (class "Default")
      (node (ref "D2") (pin "3") (pinfunction "AC_3") (pintype "passive"))
    )
    (net (code "56") (name "unconnected-(D3-AC-Pad3)") (class "Default")
      (node (ref "D3") (pin "3") (pinfunction "AC_3") (pintype "passive"))
    )
    (net (code "57") (name "unconnected-(D5-AC-Pad3)") (class "Default")
      (node (ref "D5") (pin "3") (pinfunction "AC_3") (pintype "passive"))
    )
    (net (code "58") (name "unconnected-(D6-AC-Pad3)") (class "Default")
      (node (ref "D6") (pin "3") (pinfunction "AC_3") (pintype "passive"))
    )
    (net (code "59") (name "unconnected-(D8-AC-Pad3)") (class "Default")
      (node (ref "D8") (pin "3") (pinfunction "AC_3") (pintype "passive"))
    )
    (net (code "60") (name "unconnected-(D9-AC-Pad3)") (class "Default")
      (node (ref "D9") (pin "3") (pinfunction "AC_3") (pintype "passive"))
    )
    (net (code "61") (name "unconnected-(D11-AC-Pad3)") (class "Default")
      (node (ref "D11") (pin "3") (pinfunction "AC_3") (pintype "passive"))
    )
    (net (code "62") (name "unconnected-(D12-AC-Pad3)") (class "Default")
      (node (ref "D12") (pin "3") (pinfunction "AC_3") (pintype "passive"))
    )
    (net (code "63") (name "unconnected-(D14-AC-Pad3)") (class "Default")
      (node (ref "D14") (pin "3") (pinfunction "AC_3") (pintype "passive"))
    )
    (net (code "64") (name "unconnected-(D15-AC-Pad3)") (class "Default")
      (node (ref "D15") (pin "3") (pinfunction "AC_3") (pintype "passive"))
    )
    (net (code "65") (name "unconnected-(D17-AC-Pad3)") (class "Default")
      (node (ref "D17") (pin "3") (pinfunction "AC_3") (pintype "passive"))
    )
    (net (code "66") (name "unconnected-(D18-AC-Pad3)") (class "Default")
      (node (ref "D18") (pin "3") (pinfunction "AC_3") (pintype "passive"))
    )
    (net (code "67") (name "unconnected-(P1-Pad4)") (class "Default")
      (node (ref "P1") (pin "4") (pinfunction "4_4") (pintype "passive"))
    )
    (net (code "68") (name "unconnected-(P1-Pad7)") (class "Default")
      (node (ref "P1") (pin "7") (pinfunction "7_7") (pintype "passive"))
    )
    (net (code "69") (name "unconnected-(P1-Pad8)") (class "Default")
      (node (ref "P1") (pin "8") (pinfunction "8_8") (pintype "passive"))
    )
    (net (code "70") (name "unconnected-(P1-Pad9)") (class "Default")
      (node (ref "P1") (pin "9") (pinfunction "9_9") (pintype "passive"))
    )
    (net (code "71") (name "unconnected-(P1-Pad10)") (class "Default")
      (node (ref "P1") (pin "10") (pinfunction "10_10") (pintype "passive"))
    )
    (net (code "72") (name "unconnected-(P1-Pad11)") (class "Default")
      (node (ref "P1") (pin "11") (pinfunction "11_11") (pintype "passive"))
    )
    (net (code "73") (name "unconnected-(P1-Pad12)") (class "Default")
      (node (ref "P1") (pin "12") (pinfunction "12_12") (pintype "passive"))
    )
    (net (code "74") (name "unconnected-(P1-Pad23)") (class "Default")
      (node (ref "P1") (pin "23") (pinfunction "23_23") (pintype "passive"))
    )
    (net (code "75") (name "unconnected-(P1-Pad24)") (class "Default")
      (node (ref "P1") (pin "24") (pinfunction "24_24") (pintype "passive"))
    )
    (net (code "76") (name "unconnected-(P1-Pad25)") (class "Default")
      (node (ref "P1") (pin "25") (pinfunction "25_25") (pintype "passive"))
    )
    (net (code "77") (name "unconnected-(P5-PadMP)") (class "Default")
      (node (ref "P5") (pin "MP") (pinfunction "MP_MP") (pintype "passive"))
    )
    (net (code "78") (name "unconnected-(U1A-X6-Pad2)") (class "Default")
      (node (ref "U1") (pin "2") (pinfunction "X6_2") (pintype "bidirectional"))
    )
    (net (code "79") (name "unconnected-(U1A-X7-Pad4)") (class "Default")
      (node (ref "U1") (pin "4") (pinfunction "X7_4") (pintype "bidirectional"))
    )
  )
)
